# ui_ring_v1.net
KiCad netlist of a schematic drawn in EasyEDA Pro
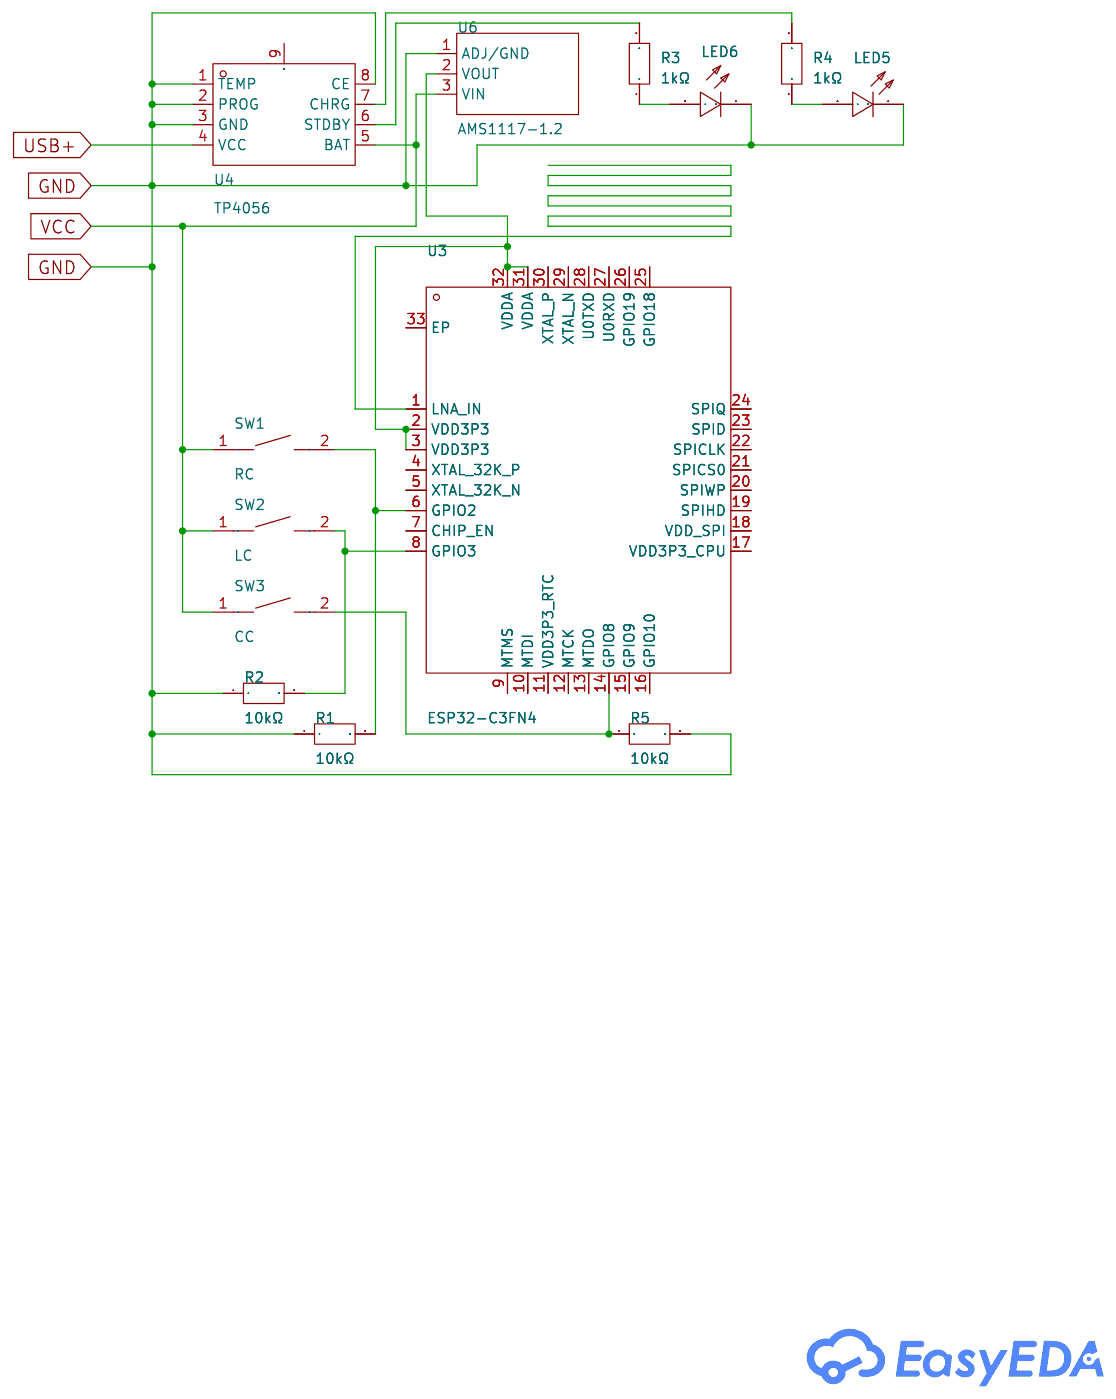
[diagram p0: schematic sheet]

(export (version "E")
  (design (tool "Eeschema 10.0.6"))
  (components
    (comp (ref "LED5")
      (value "19-217/BHC-ZL1M2RY/3T")
      (footprint "easyedapro:LED0603-FD_BLUE")
      (fields (field (name "Manufacturer") "EVERLIGHT(亿光)"))
      (libsource (lib "easyedapro") (part "19-217/BHC-ZL1M2RY/3T"))
    )
    (comp (ref "LED6")
      (value "19-217/R6C-AL1M2VY/3T")
      (footprint "easyedapro:LED0603-RD")
      (fields (field (name "Manufacturer") "EVERLIGHT(亿光)"))
      (libsource (lib "easyedapro") (part "19-217/R6C-AL1M2VY/3T"))
    )
    (comp (ref "R1")
      (value "10kΩ")
      (footprint "easyedapro:R0402")
      (fields (field (name "Manufacturer Part") "AC0402FR-1310KL") (field (name "Manufacturer") "YAGEO(国巨)"))
      (libsource (lib "easyedapro") (part "AC0402FR-1310KL"))
    )
    (comp (ref "R2")
      (value "10kΩ")
      (footprint "easyedapro:R0402")
      (fields (field (name "Manufacturer Part") "AC0402FR-1310KL") (field (name "Manufacturer") "YAGEO(国巨)"))
      (libsource (lib "easyedapro") (part "AC0402FR-1310KL"))
    )
    (comp (ref "R3")
      (value "1kΩ")
      (footprint "easyedapro:R0402")
      (fields (field (name "Manufacturer Part") "AC0402FR-1310KL") (field (name "Manufacturer") "YAGEO(国巨)"))
      (libsource (lib "easyedapro") (part "AC0402FR-1310KL"))
    )
    (comp (ref "R4")
      (value "1kΩ")
      (footprint "easyedapro:R0402")
      (fields (field (name "Manufacturer Part") "AC0402FR-1310KL") (field (name "Manufacturer") "YAGEO(国巨)"))
      (libsource (lib "easyedapro") (part "AC0402FR-1310KL"))
    )
    (comp (ref "R5")
      (value "10kΩ")
      (footprint "easyedapro:R0402")
      (fields (field (name "Manufacturer Part") "AC0402FR-1310KL") (field (name "Manufacturer") "YAGEO(国巨)"))
      (libsource (lib "easyedapro") (part "AC0402FR-1310KL"))
    )
    (comp (ref "SW1")
      (value "RC")
      (footprint "easyedapro:SW-SMD_L3.9-W3.0-P4.45")
      (fields (field (name "Manufacturer") "XUNPU(讯普)"))
      (libsource (lib "easyedapro") (part "TS-1088-AR02016"))
    )
    (comp (ref "SW2")
      (value "LC")
      (footprint "easyedapro:SW-SMD_L3.9-W3.0-P4.45")
      (fields (field (name "Manufacturer") "XUNPU(讯普)"))
      (libsource (lib "easyedapro") (part "TS-1088-AR02016"))
    )
    (comp (ref "SW3")
      (value "CC")
      (footprint "easyedapro:SW-SMD_L3.9-W3.0-P4.45")
      (fields (field (name "Manufacturer") "XUNPU(讯普)"))
      (libsource (lib "easyedapro") (part "TS-1088-AR02016"))
    )
    (comp (ref "U3")
      (value "ESP32-C3FN4")
      (footprint "easyedapro:QFN-32_L5.0-W5.0-P0.50-BL-EP3.7")
      (fields (field (name "Manufacturer") "ESPRESSIF(乐鑫)"))
      (libsource (lib "easyedapro") (part "ESP32-C3FN4"))
    )
    (comp (ref "U4")
      (value "TP4056")
      (footprint "easyedapro:ESOP-8_L4.9-W3.9-P1.27-LS6.0-BL-EP-4")
      (fields (field (name "Manufacturer") "YONGYUTAI(永裕泰)"))
      (libsource (lib "easyedapro") (part "TP4056_C20199357"))
    )
    (comp (ref "U6")
      (value "AMS1117-1.2")
      (footprint "easyedapro:SOT-89-3_L4.5-W2.5-P1.50-LS4.2-BR")
      (fields (field (name "Manufacturer") "JSMSEMI(杰盛微)"))
      (libsource (lib "easyedapro") (part "AMS1117-1.2_C963407"))
    )
  )
  (nets
    (net (code "1") (name "GND") (class "Default")
      (node (ref "LED5") (pin "1") (pinfunction "C_1") (pintype "input"))
      (node (ref "LED6") (pin "1") (pinfunction "C_1") (pintype "input"))
      (node (ref "R1") (pin "1") (pinfunction "1_1") (pintype "unspecified"))
      (node (ref "R2") (pin "1") (pinfunction "1_1") (pintype "unspecified"))
      (node (ref "R5") (pin "2") (pinfunction "2_2") (pintype "unspecified"))
      (node (ref "U4") (pin "1") (pinfunction "TEMP_1") (pintype "unspecified"))
      (node (ref "U4") (pin "2") (pinfunction "PROG_2") (pintype "unspecified"))
      (node (ref "U4") (pin "3") (pinfunction "GND_3") (pintype "unspecified"))
      (node (ref "U4") (pin "8") (pinfunction "CE_8") (pintype "unspecified"))
      (node (ref "U6") (pin "1") (pinfunction "ADJ/GND_1") (pintype "unspecified"))
    )
    (net (code "2") (name "Net-(LED5-A)") (class "Default")
      (node (ref "LED5") (pin "2") (pinfunction "A_2") (pintype "input"))
      (node (ref "R4") (pin "1") (pinfunction "1_1") (pintype "unspecified"))
    )
    (net (code "3") (name "Net-(LED6-A)") (class "Default")
      (node (ref "LED6") (pin "2") (pinfunction "A_2") (pintype "input"))
      (node (ref "R3") (pin "1") (pinfunction "1_1") (pintype "unspecified"))
    )
    (net (code "4") (name "Net-(U3-GPIO2)") (class "Default")
      (node (ref "R1") (pin "2") (pinfunction "2_2") (pintype "unspecified"))
      (node (ref "SW1") (pin "2") (pinfunction "2_2") (pintype "unspecified"))
      (node (ref "U3") (pin "6") (pinfunction "GPIO2_6") (pintype "unspecified"))
    )
    (net (code "5") (name "Net-(U3-GPIO3)") (class "Default")
      (node (ref "R2") (pin "2") (pinfunction "2_2") (pintype "unspecified"))
      (node (ref "SW2") (pin "2") (pinfunction "2_2") (pintype "unspecified"))
      (node (ref "U3") (pin "8") (pinfunction "GPIO3_8") (pintype "unspecified"))
    )
    (net (code "6") (name "Net-(U3-GPIO8)") (class "Default")
      (node (ref "R5") (pin "1") (pinfunction "1_1") (pintype "unspecified"))
      (node (ref "SW3") (pin "2") (pinfunction "2_2") (pintype "unspecified"))
      (node (ref "U3") (pin "14") (pinfunction "GPIO8_14") (pintype "unspecified"))
    )
    (net (code "7") (name "Net-(U4-CHRG)") (class "Default")
      (node (ref "R4") (pin "2") (pinfunction "2_2") (pintype "unspecified"))
      (node (ref "U4") (pin "7") (pinfunction "CHRG_7") (pintype "unspecified"))
    )
    (net (code "8") (name "Net-(U4-STDBY)") (class "Default")
      (node (ref "R3") (pin "2") (pinfunction "2_2") (pintype "unspecified"))
      (node (ref "U4") (pin "6") (pinfunction "STDBY_6") (pintype "unspecified"))
    )
    (net (code "9") (name "Net-(U6-VOUT)") (class "Default")
      (node (ref "U3") (pin "2") (pinfunction "VDD3P3_2") (pintype "unspecified"))
      (node (ref "U3") (pin "3") (pinfunction "VDD3P3_3") (pintype "unspecified"))
      (node (ref "U3") (pin "31") (pinfunction "VDDA_31") (pintype "unspecified"))
      (node (ref "U3") (pin "32") (pinfunction "VDDA_32") (pintype "unspecified"))
      (node (ref "U6") (pin "2") (pinfunction "VOUT_2") (pintype "unspecified"))
    )
    (net (code "10") (name "USB+") (class "Default")
      (node (ref "U4") (pin "4") (pinfunction "VCC_4") (pintype "unspecified"))
    )
    (net (code "11") (name "VCC") (class "Default")
      (node (ref "SW1") (pin "1") (pinfunction "1_1") (pintype "unspecified"))
      (node (ref "SW2") (pin "1") (pinfunction "1_1") (pintype "unspecified"))
      (node (ref "SW3") (pin "1") (pinfunction "1_1") (pintype "unspecified"))
      (node (ref "U4") (pin "5") (pinfunction "BAT_5") (pintype "unspecified"))
      (node (ref "U6") (pin "3") (pinfunction "VIN_3") (pintype "unspecified"))
    )
    (net (code "12") (name "unconnected-(U3-CHIP_EN-Pad7)") (class "Default")
      (node (ref "U3") (pin "7") (pinfunction "CHIP_EN_7") (pintype "unspecified"))
    )
    (net (code "13") (name "unconnected-(U3-EP-Pad33)") (class "Default")
      (node (ref "U3") (pin "33") (pinfunction "EP_33") (pintype "unspecified"))
    )
    (net (code "14") (name "unconnected-(U3-GPIO9-Pad15)") (class "Default")
      (node (ref "U3") (pin "15") (pinfunction "GPIO9_15") (pintype "unspecified"))
    )
    (net (code "15") (name "unconnected-(U3-GPIO10-Pad16)") (class "Default")
      (node (ref "U3") (pin "16") (pinfunction "GPIO10_16") (pintype "unspecified"))
    )
    (net (code "16") (name "unconnected-(U3-GPIO18-Pad25)") (class "Default")
      (node (ref "U3") (pin "25") (pinfunction "GPIO18_25") (pintype "unspecified"))
    )
    (net (code "17") (name "unconnected-(U3-GPIO19-Pad26)") (class "Default")
      (node (ref "U3") (pin "26") (pinfunction "GPIO19_26") (pintype "unspecified"))
    )
    (net (code "18") (name "unconnected-(U3-LNA_IN-Pad1)") (class "Default")
      (node (ref "U3") (pin "1") (pinfunction "LNA_IN_1") (pintype "unspecified"))
    )
    (net (code "19") (name "unconnected-(U3-MTCK-Pad12)") (class "Default")
      (node (ref "U3") (pin "12") (pinfunction "MTCK_12") (pintype "unspecified"))
    )
    (net (code "20") (name "unconnected-(U3-MTDI-Pad10)") (class "Default")
      (node (ref "U3") (pin "10") (pinfunction "MTDI_10") (pintype "unspecified"))
    )
    (net (code "21") (name "unconnected-(U3-MTDO-Pad13)") (class "Default")
      (node (ref "U3") (pin "13") (pinfunction "MTDO_13") (pintype "unspecified"))
    )
    (net (code "22") (name "unconnected-(U3-MTMS-Pad9)") (class "Default")
      (node (ref "U3") (pin "9") (pinfunction "MTMS_9") (pintype "unspecified"))
    )
    (net (code "23") (name "unconnected-(U3-SPICLK-Pad22)") (class "Default")
      (node (ref "U3") (pin "22") (pinfunction "SPICLK_22") (pintype "unspecified"))
    )
    (net (code "24") (name "unconnected-(U3-SPICS0-Pad21)") (class "Default")
      (node (ref "U3") (pin "21") (pinfunction "SPICS0_21") (pintype "unspecified"))
    )
    (net (code "25") (name "unconnected-(U3-SPID-Pad23)") (class "Default")
      (node (ref "U3") (pin "23") (pinfunction "SPID_23") (pintype "unspecified"))
    )
    (net (code "26") (name "unconnected-(U3-SPIHD-Pad19)") (class "Default")
      (node (ref "U3") (pin "19") (pinfunction "SPIHD_19") (pintype "unspecified"))
    )
    (net (code "27") (name "unconnected-(U3-SPIQ-Pad24)") (class "Default")
      (node (ref "U3") (pin "24") (pinfunction "SPIQ_24") (pintype "unspecified"))
    )
    (net (code "28") (name "unconnected-(U3-SPIWP-Pad20)") (class "Default")
      (node (ref "U3") (pin "20") (pinfunction "SPIWP_20") (pintype "unspecified"))
    )
    (net (code "29") (name "unconnected-(U3-U0RXD-Pad27)") (class "Default")
      (node (ref "U3") (pin "27") (pinfunction "U0RXD_27") (pintype "unspecified"))
    )
    (net (code "30") (name "unconnected-(U3-U0TXD-Pad28)") (class "Default")
      (node (ref "U3") (pin "28") (pinfunction "U0TXD_28") (pintype "unspecified"))
    )
    (net (code "31") (name "unconnected-(U3-VDD3P3_CPU-Pad17)") (class "Default")
      (node (ref "U3") (pin "17") (pinfunction "VDD3P3_CPU_17") (pintype "unspecified"))
    )
    (net (code "32") (name "unconnected-(U3-VDD3P3_RTC-Pad11)") (class "Default")
      (node (ref "U3") (pin "11") (pinfunction "VDD3P3_RTC_11") (pintype "unspecified"))
    )
    (net (code "33") (name "unconnected-(U3-VDD_SPI-Pad18)") (class "Default")
      (node (ref "U3") (pin "18") (pinfunction "VDD_SPI_18") (pintype "unspecified"))
    )
    (net (code "34") (name "unconnected-(U3-XTAL_32K_N-Pad5)") (class "Default")
      (node (ref "U3") (pin "5") (pinfunction "XTAL_32K_N_5") (pintype "unspecified"))
    )
    (net (code "35") (name "unconnected-(U3-XTAL_32K_P-Pad4)") (class "Default")
      (node (ref "U3") (pin "4") (pinfunction "XTAL_32K_P_4") (pintype "unspecified"))
    )
    (net (code "36") (name "unconnected-(U3-XTAL_N-Pad29)") (class "Default")
      (node (ref "U3") (pin "29") (pinfunction "XTAL_N_29") (pintype "unspecified"))
    )
    (net (code "37") (name "unconnected-(U3-XTAL_P-Pad30)") (class "Default")
      (node (ref "U3") (pin "30") (pinfunction "XTAL_P_30") (pintype "unspecified"))
    )
    (net (code "38") (name "unconnected-(U4-PAD-Pad9)") (class "Default")
      (node (ref "U4") (pin "9") (pinfunction "PAD_9") (pintype "unspecified"))
    )
  )
)
